# HiSpeedADC.net
KiCad netlist of a schematic drawn in Altium Designer
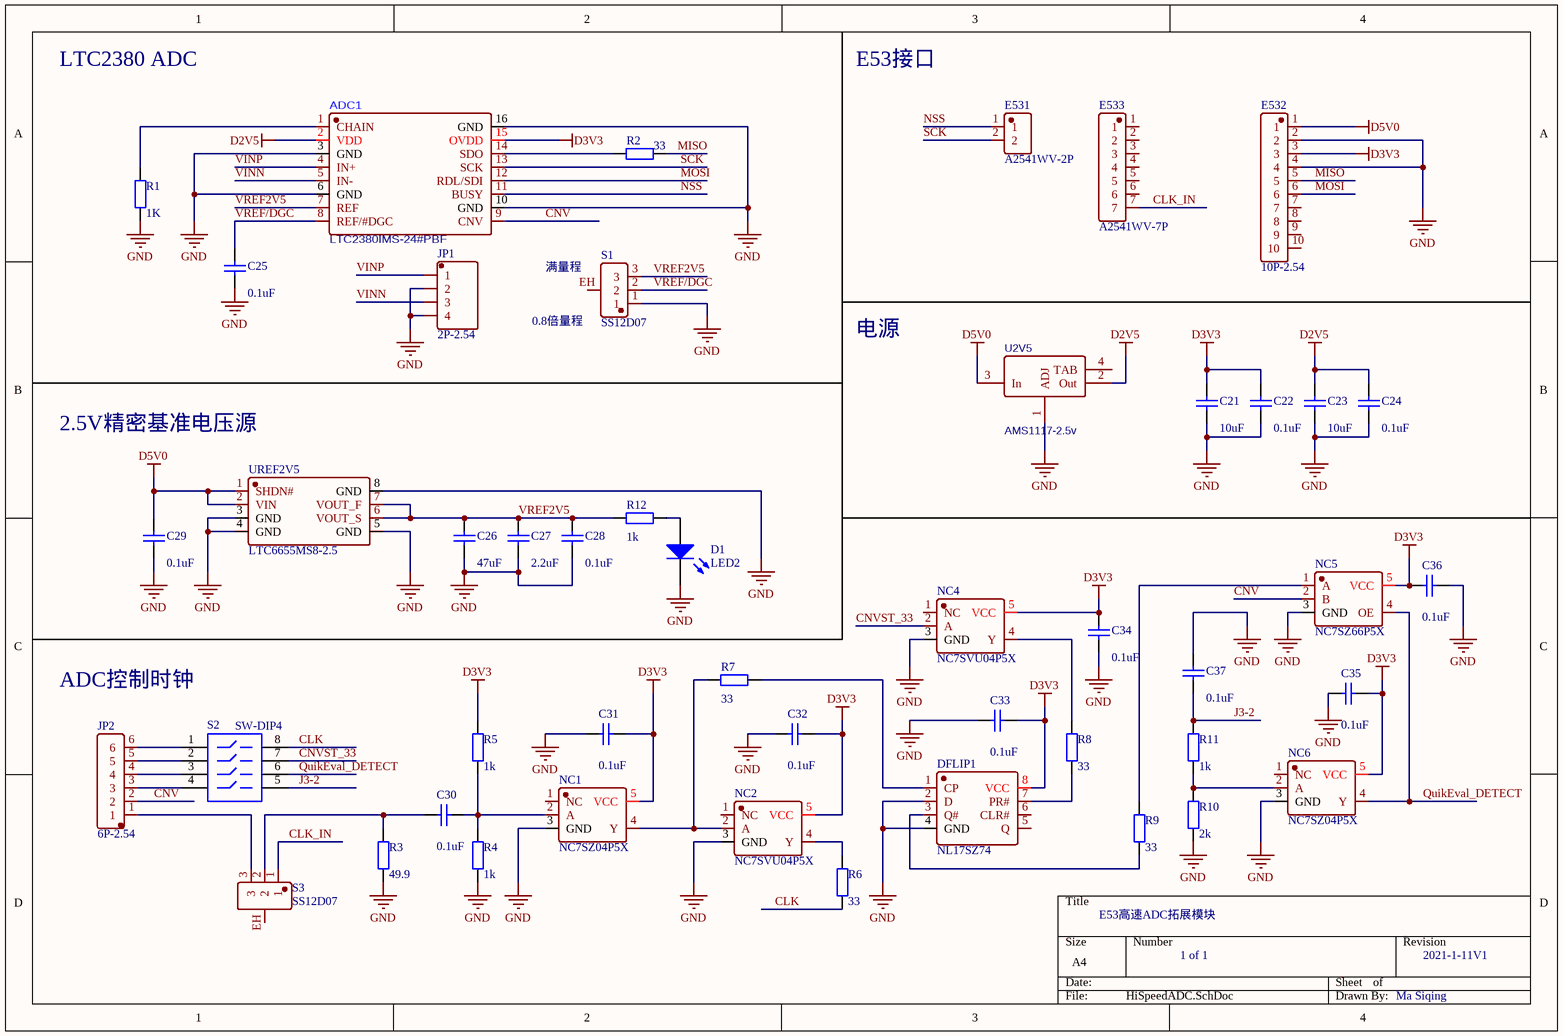
[diagram p0: HiSpeedADC.SchDoc]

(export (version "E")
  (design (tool "Eeschema 10.0.6"))
  (components
    (comp (ref "ADC1")
      (value "LTC2380IMS-24#PBF")
      (footprint "MSOP-16_L4.0-W3.0-P0.50-LS4.9-BL")
      (libsource (lib "NBIoT") (part "LTC2380IMS-24#PBF"))
    )
    (comp (ref "C21")
      (value "10uF")
      (footprint "C1206")
      (description "Capacitor (Semiconductor SIM Model)")
      (fields (field (name "PUBLISHER") "Altium Limited"))
      (libsource (lib "Miscellaneous Devices") (part "Cap Semi"))
    )
    (comp (ref "C22")
      (value "0.1uF")
      (footprint "C1206")
      (description "Capacitor (Semiconductor SIM Model)")
      (fields (field (name "PUBLISHER") "Altium Limited"))
      (libsource (lib "Miscellaneous Devices") (part "Cap Semi"))
    )
    (comp (ref "C23")
      (value "10uF")
      (footprint "C1206")
      (description "Capacitor (Semiconductor SIM Model)")
      (fields (field (name "PUBLISHER") "Altium Limited"))
      (libsource (lib "Miscellaneous Devices") (part "Cap Semi"))
    )
    (comp (ref "C24")
      (value "0.1uF")
      (footprint "C1206")
      (description "Capacitor (Semiconductor SIM Model)")
      (fields (field (name "PUBLISHER") "Altium Limited"))
      (libsource (lib "Miscellaneous Devices") (part "Cap Semi"))
    )
    (comp (ref "C25")
      (value "0.1uF")
      (footprint "C1206")
      (description "Capacitor (Semiconductor SIM Model)")
      (fields (field (name "PUBLISHER") "Altium Limited"))
      (libsource (lib "Miscellaneous Devices") (part "Cap Semi"))
    )
    (comp (ref "C26")
      (value "47uF")
      (footprint "C1206")
      (description "Capacitor (Semiconductor SIM Model)")
      (fields (field (name "PUBLISHER") "Altium Limited"))
      (libsource (lib "Miscellaneous Devices") (part "Cap Semi"))
    )
    (comp (ref "C27")
      (value "2.2uF")
      (footprint "C1206")
      (description "Capacitor (Semiconductor SIM Model)")
      (fields (field (name "PUBLISHER") "Altium Limited"))
      (libsource (lib "Miscellaneous Devices") (part "Cap Semi"))
    )
    (comp (ref "C28")
      (value "0.1uF")
      (footprint "C1206")
      (description "Capacitor (Semiconductor SIM Model)")
      (fields (field (name "PUBLISHER") "Altium Limited"))
      (libsource (lib "Miscellaneous Devices") (part "Cap Semi"))
    )
    (comp (ref "C29")
      (value "0.1uF")
      (footprint "C1206")
      (description "Capacitor (Semiconductor SIM Model)")
      (fields (field (name "PUBLISHER") "Altium Limited"))
      (libsource (lib "Miscellaneous Devices") (part "Cap Semi"))
    )
    (comp (ref "C30")
      (value "0.1uF")
      (footprint "C1206")
      (description "Capacitor (Semiconductor SIM Model)")
      (fields (field (name "PUBLISHER") "Altium Limited"))
      (libsource (lib "Miscellaneous Devices") (part "Cap Semi"))
    )
    (comp (ref "C31")
      (value "0.1uF")
      (footprint "C1206")
      (description "Capacitor (Semiconductor SIM Model)")
      (fields (field (name "PUBLISHER") "Altium Limited"))
      (libsource (lib "Miscellaneous Devices") (part "Cap Semi"))
    )
    (comp (ref "C32")
      (value "0.1uF")
      (footprint "C1206")
      (description "Capacitor (Semiconductor SIM Model)")
      (fields (field (name "PUBLISHER") "Altium Limited"))
      (libsource (lib "Miscellaneous Devices") (part "Cap Semi"))
    )
    (comp (ref "C33")
      (value "0.1uF")
      (footprint "C1206")
      (description "Capacitor (Semiconductor SIM Model)")
      (fields (field (name "PUBLISHER") "Altium Limited"))
      (libsource (lib "Miscellaneous Devices") (part "Cap Semi"))
    )
    (comp (ref "C34")
      (value "0.1uF")
      (footprint "C1206")
      (description "Capacitor (Semiconductor SIM Model)")
      (fields (field (name "PUBLISHER") "Altium Limited"))
      (libsource (lib "Miscellaneous Devices") (part "Cap Semi"))
    )
    (comp (ref "C35")
      (value "0.1uF")
      (footprint "C1206")
      (description "Capacitor (Semiconductor SIM Model)")
      (fields (field (name "PUBLISHER") "Altium Limited"))
      (libsource (lib "Miscellaneous Devices") (part "Cap Semi"))
    )
    (comp (ref "C36")
      (value "0.1uF")
      (footprint "C1206")
      (description "Capacitor (Semiconductor SIM Model)")
      (fields (field (name "PUBLISHER") "Altium Limited"))
      (libsource (lib "Miscellaneous Devices") (part "Cap Semi"))
    )
    (comp (ref "C37")
      (value "0.1uF")
      (footprint "C1206")
      (description "Capacitor (Semiconductor SIM Model)")
      (fields (field (name "PUBLISHER") "Altium Limited"))
      (libsource (lib "Miscellaneous Devices") (part "Cap Semi"))
    )
    (comp (ref "D1")
      (value "LED2")
      (footprint "3.2X1.6X1.1")
      (description "Typical RED, GREEN, YELLOW, AMBER GaAs LED")
      (fields (field (name "PUBLISHER") "Altium Limited"))
      (libsource (lib "Miscellaneous Devices") (part "LED2"))
    )
    (comp (ref "DFLIP1")
      (value "NL17SZ74")
      (footprint "US-8_L2.4-W2.1-P0.50-LS3.2-BR")
      (libsource (lib "NBIoT") (part "NL17SZ74"))
    )
    (comp (ref "E531")
      (value "A2541WV-2P")
      (footprint "HDR-TH_P2.54-H-M_A2541WV-2P")
      (libsource (lib "NBIoT") (part "A2541WV-2P"))
    )
    (comp (ref "E532")
      (value "10P-2.54")
      (footprint "HDR-TH_10P-P2.54-V")
      (libsource (lib "NBIoT") (part "10P-2.54"))
    )
    (comp (ref "E533")
      (value "A2541WV-7P")
      (footprint "HDR-TH_7P-P2.54-V")
      (libsource (lib "NBIoT") (part "A2541WV-7P"))
    )
    (comp (ref "JP1")
      (value "2P-2.54")
      (footprint "HDR-TH_4P-P2.54-V")
      (libsource (lib "NBIoT") (part "2P-2.54"))
    )
    (comp (ref "JP2")
      (value "6P-2.54")
      (footprint "HDR-TH_6P-P2.54-V")
      (libsource (lib "NBIoT") (part "6P-2.54"))
    )
    (comp (ref "NC1")
      (value "NC7SZ04P5X")
      (footprint "SC-70-5_L2.1-W1.3-P0.65-LS2.1-BR")
      (libsource (lib "NBIoT") (part "NC7SZ04P5X"))
    )
    (comp (ref "NC2")
      (value "NC7SVU04P5X")
      (footprint "SC-70-5_L2.1-W1.3-P0.65-LS2.1-BL")
      (libsource (lib "NBIoT") (part "NC7SVU04P5X"))
    )
    (comp (ref "NC4")
      (value "NC7SVU04P5X")
      (footprint "SC-70-5_L2.1-W1.3-P0.65-LS2.1-BL")
      (libsource (lib "NBIoT") (part "NC7SVU04P5X"))
    )
    (comp (ref "NC5")
      (value "NC7SZ66P5X")
      (footprint "SC-70-5_L2.1-W1.3-P0.65-LS2.1-BL")
      (libsource (lib "NBIoT") (part "NC7SZ66P5X"))
    )
    (comp (ref "NC6")
      (value "NC7SZ04P5X")
      (footprint "SC-70-5_L2.1-W1.3-P0.65-LS2.1-BR")
      (libsource (lib "NBIoT") (part "NC7SZ04P5X"))
    )
    (comp (ref "R1")
      (value "1K")
      (footprint "6-0805_N")
      (description "Resistor")
      (fields (field (name "PUBLISHER") "Altium Limited"))
      (libsource (lib "Miscellaneous Devices") (part "Res2"))
    )
    (comp (ref "R2")
      (value "33")
      (footprint "6-0805_N")
      (description "Resistor")
      (fields (field (name "PUBLISHER") "Altium Limited"))
      (libsource (lib "") (part "Res2_1"))
    )
    (comp (ref "R3")
      (value "49.9")
      (footprint "6-0805_N")
      (description "Resistor")
      (fields (field (name "PUBLISHER") "Altium Limited"))
      (libsource (lib "") (part "Res2_2"))
    )
    (comp (ref "R4")
      (value "1k")
      (footprint "6-0805_N")
      (description "Resistor")
      (fields (field (name "PUBLISHER") "Altium Limited"))
      (libsource (lib "") (part "Res2_2"))
    )
    (comp (ref "R5")
      (value "1k")
      (footprint "6-0805_N")
      (description "Resistor")
      (fields (field (name "PUBLISHER") "Altium Limited"))
      (libsource (lib "") (part "Res2_2"))
    )
    (comp (ref "R6")
      (value "33")
      (footprint "6-0805_N")
      (description "Resistor")
      (fields (field (name "PUBLISHER") "Altium Limited"))
      (libsource (lib "Miscellaneous Devices") (part "Res2"))
    )
    (comp (ref "R7")
      (value "33")
      (footprint "6-0805_N")
      (description "Resistor")
      (fields (field (name "PUBLISHER") "Altium Limited"))
      (libsource (lib "") (part "Res2_1"))
    )
    (comp (ref "R8")
      (value "33")
      (footprint "6-0805_N")
      (description "Resistor")
      (fields (field (name "PUBLISHER") "Altium Limited"))
      (libsource (lib "") (part "Res2_2"))
    )
    (comp (ref "R9")
      (value "33")
      (footprint "6-0805_N")
      (description "Resistor")
      (fields (field (name "PUBLISHER") "Altium Limited"))
      (libsource (lib "Miscellaneous Devices") (part "Res2"))
    )
    (comp (ref "R10")
      (value "2k")
      (footprint "6-0805_N")
      (description "Resistor")
      (fields (field (name "PUBLISHER") "Altium Limited"))
      (libsource (lib "Miscellaneous Devices") (part "Res2"))
    )
    (comp (ref "R11")
      (value "1k")
      (footprint "6-0805_N")
      (description "Resistor")
      (fields (field (name "PUBLISHER") "Altium Limited"))
      (libsource (lib "Miscellaneous Devices") (part "Res2"))
    )
    (comp (ref "R12")
      (value "1k")
      (footprint "6-0805_N")
      (description "Resistor")
      (fields (field (name "PUBLISHER") "Altium Limited"))
      (libsource (lib "") (part "Res2_1"))
    )
    (comp (ref "S1")
      (value "SS12D07")
      (footprint "SW-TH_SS-12D07-X-X")
      (libsource (lib "NBIoT") (part "SS12D07"))
    )
    (comp (ref "S2")
      (value "SW-DIP4")
      (footprint "DIP-8")
      (description "DIP Switch")
      (fields (field (name "PUBLISHER") "Altium Limited"))
      (libsource (lib "Miscellaneous Devices") (part "SW-DIP4"))
    )
    (comp (ref "S3")
      (value "SS12D07")
      (footprint "SW-TH_SS-12D07-X-X")
      (libsource (lib "NBIoT") (part "SS12D07"))
    )
    (comp (ref "U2V5")
      (value "AMS1117-2.5v")
      (footprint "SOT-223_L6.7-W3.5-P2.30-BR")
      (fields
        (field (name "BOM_MANUFACTURER PART") "AMS1117-ADJ")
        (field (name "BOM_SUPPLIER PART") "C6188")
        (field (name "CONTRIBUTOR") "GerryChen")
      )
      (libsource (lib "NBIoT") (part "AMS1117-ADJ"))
    )
    (comp (ref "UREF2V5")
      (value "LTC6655MS8-2.5")
      (footprint "US-8_L2.4-W2.1-P0.50-LS3.2-BR")
      (libsource (lib "NBIoT") (part "LTC6655MS8-5"))
    )
  )
  (nets
    (net (code "1") (name "/CLK") (class "Default")
      (node (ref "R6") (pin "1") (pinfunction "1_1") (pintype "passive"))
      (node (ref "S2") (pin "8") (pinfunction "8_8") (pintype "passive"))
    )
    (net (code "2") (name "/CLK_IN") (class "Default")
      (node (ref "E533") (pin "7") (pinfunction "7_7") (pintype "passive"))
      (node (ref "S3") (pin "1") (pinfunction "1_1") (pintype "passive"))
    )
    (net (code "3") (name "/CNV") (class "Default")
      (node (ref "ADC1") (pin "9") (pinfunction "CNV_9") (pintype "passive"))
      (node (ref "JP2") (pin "2") (pinfunction "2_2") (pintype "passive"))
      (node (ref "NC5") (pin "2") (pinfunction "B_2") (pintype "passive"))
    )
    (net (code "4") (name "/CNVST_33") (class "Default")
      (node (ref "NC4") (pin "2") (pinfunction "A_2") (pintype "passive"))
      (node (ref "S2") (pin "7") (pinfunction "7_7") (pintype "passive"))
    )
    (net (code "5") (name "/J3-2") (class "Default")
      (node (ref "C37") (pin "1") (pinfunction "1_1") (pintype "passive"))
      (node (ref "R11") (pin "2") (pinfunction "2_2") (pintype "passive"))
      (node (ref "S2") (pin "5") (pinfunction "5_5") (pintype "passive"))
    )
    (net (code "6") (name "/MISO") (class "Default")
      (node (ref "E532") (pin "5") (pinfunction "5_5") (pintype "passive"))
      (node (ref "R2") (pin "1") (pinfunction "1_1") (pintype "passive"))
    )
    (net (code "7") (name "/MOSI") (class "Default")
      (node (ref "ADC1") (pin "12") (pinfunction "RDL/SDI_12") (pintype "passive"))
      (node (ref "E532") (pin "6") (pinfunction "6_6") (pintype "passive"))
    )
    (net (code "8") (name "/NSS") (class "Default")
      (node (ref "ADC1") (pin "11") (pinfunction "BUSY_11") (pintype "passive"))
      (node (ref "E531") (pin "1") (pinfunction "1_1") (pintype "passive"))
    )
    (net (code "9") (name "/QuikEval_DETECT") (class "Default")
      (node (ref "NC5") (pin "4") (pinfunction "OE_4") (pintype "passive"))
      (node (ref "NC6") (pin "4") (pinfunction "Y_4") (pintype "passive"))
      (node (ref "S2") (pin "6") (pinfunction "6_6") (pintype "passive"))
    )
    (net (code "10") (name "/SCK") (class "Default")
      (node (ref "ADC1") (pin "13") (pinfunction "SCK_13") (pintype "passive"))
      (node (ref "E531") (pin "2") (pinfunction "2_2") (pintype "passive"))
    )
    (net (code "11") (name "/VINN") (class "Default")
      (node (ref "ADC1") (pin "5") (pinfunction "IN-_5") (pintype "passive"))
      (node (ref "JP1") (pin "3") (pinfunction "3_3") (pintype "passive"))
    )
    (net (code "12") (name "/VINP") (class "Default")
      (node (ref "ADC1") (pin "4") (pinfunction "IN+_4") (pintype "passive"))
      (node (ref "JP1") (pin "1") (pinfunction "1_1") (pintype "passive"))
    )
    (net (code "13") (name "/VREF2V5") (class "Default")
      (node (ref "ADC1") (pin "7") (pinfunction "REF_7") (pintype "passive"))
      (node (ref "C26") (pin "1") (pinfunction "1_1") (pintype "passive"))
      (node (ref "C27") (pin "1") (pinfunction "1_1") (pintype "passive"))
      (node (ref "C28") (pin "1") (pinfunction "1_1") (pintype "passive"))
      (node (ref "R12") (pin "2") (pinfunction "2_2") (pintype "passive"))
      (node (ref "S1") (pin "3") (pinfunction "3_3") (pintype "passive"))
      (node (ref "UREF2V5") (pin "6") (pinfunction "VOUT_S_6") (pintype "passive"))
      (node (ref "UREF2V5") (pin "7") (pinfunction "VOUT_F_7") (pintype "passive"))
    )
    (net (code "14") (name "/VREF{slash}DGC") (class "Default")
      (node (ref "ADC1") (pin "8") (pinfunction "REF/#DGC_8") (pintype "passive"))
      (node (ref "C25") (pin "1") (pinfunction "1_1") (pintype "passive"))
      (node (ref "S1") (pin "2") (pinfunction "2_2") (pintype "passive"))
    )
    (net (code "15") (name "D2V5") (class "Default")
      (node (ref "ADC1") (pin "2") (pinfunction "VDD_2") (pintype "passive"))
      (node (ref "C23") (pin "1") (pinfunction "1_1") (pintype "passive"))
      (node (ref "C24") (pin "1") (pinfunction "1_1") (pintype "passive"))
      (node (ref "U2V5") (pin "2") (pinfunction "Out_2") (pintype "passive"))
    )
    (net (code "16") (name "D3V3") (class "Default")
      (node (ref "ADC1") (pin "15") (pinfunction "OVDD_15") (pintype "passive"))
      (node (ref "C21") (pin "1") (pinfunction "1_1") (pintype "passive"))
      (node (ref "C22") (pin "1") (pinfunction "1_1") (pintype "passive"))
      (node (ref "C31") (pin "2") (pinfunction "2_2") (pintype "passive"))
      (node (ref "C32") (pin "2") (pinfunction "2_2") (pintype "passive"))
      (node (ref "C33") (pin "1") (pinfunction "1_1") (pintype "passive"))
      (node (ref "C34") (pin "1") (pinfunction "1_1") (pintype "passive"))
      (node (ref "C35") (pin "2") (pinfunction "2_2") (pintype "passive"))
      (node (ref "C36") (pin "1") (pinfunction "1_1") (pintype "passive"))
      (node (ref "DFLIP1") (pin "8") (pinfunction "VCC_8") (pintype "passive"))
      (node (ref "E532") (pin "3") (pinfunction "3_3") (pintype "passive"))
      (node (ref "NC1") (pin "5") (pinfunction "VCC_5") (pintype "passive"))
      (node (ref "NC2") (pin "5") (pinfunction "VCC_5") (pintype "passive"))
      (node (ref "NC4") (pin "5") (pinfunction "VCC_5") (pintype "passive"))
      (node (ref "NC5") (pin "5") (pinfunction "VCC_5") (pintype "passive"))
      (node (ref "NC6") (pin "5") (pinfunction "VCC_5") (pintype "passive"))
      (node (ref "R5") (pin "1") (pinfunction "1_1") (pintype "passive"))
    )
    (net (code "17") (name "D5V0") (class "Default")
      (node (ref "C29") (pin "1") (pinfunction "1_1") (pintype "passive"))
      (node (ref "E532") (pin "1") (pinfunction "1_1") (pintype "passive"))
      (node (ref "U2V5") (pin "3") (pinfunction "In_3") (pintype "passive"))
      (node (ref "UREF2V5") (pin "1") (pinfunction "SHDN#_1") (pintype "passive"))
      (node (ref "UREF2V5") (pin "2") (pinfunction "VIN_2") (pintype "passive"))
    )
    (net (code "18") (name "GND") (class "Default")
      (node (ref "ADC1") (pin "10") (pinfunction "GND_10") (pintype "passive"))
      (node (ref "ADC1") (pin "16") (pinfunction "GND_16") (pintype "passive"))
      (node (ref "ADC1") (pin "3") (pinfunction "GND_3") (pintype "passive"))
      (node (ref "ADC1") (pin "6") (pinfunction "GND_6") (pintype "passive"))
      (node (ref "C21") (pin "2") (pinfunction "2_2") (pintype "passive"))
      (node (ref "C22") (pin "2") (pinfunction "2_2") (pintype "passive"))
      (node (ref "C23") (pin "2") (pinfunction "2_2") (pintype "passive"))
      (node (ref "C24") (pin "2") (pinfunction "2_2") (pintype "passive"))
      (node (ref "C25") (pin "2") (pinfunction "2_2") (pintype "passive"))
      (node (ref "C26") (pin "2") (pinfunction "2_2") (pintype "passive"))
      (node (ref "C27") (pin "2") (pinfunction "2_2") (pintype "passive"))
      (node (ref "C28") (pin "2") (pinfunction "2_2") (pintype "passive"))
      (node (ref "C29") (pin "2") (pinfunction "2_2") (pintype "passive"))
      (node (ref "C31") (pin "1") (pinfunction "1_1") (pintype "passive"))
      (node (ref "C32") (pin "1") (pinfunction "1_1") (pintype "passive"))
      (node (ref "C33") (pin "2") (pinfunction "2_2") (pintype "passive"))
      (node (ref "C34") (pin "2") (pinfunction "2_2") (pintype "passive"))
      (node (ref "C35") (pin "1") (pinfunction "1_1") (pintype "passive"))
      (node (ref "C36") (pin "2") (pinfunction "2_2") (pintype "passive"))
      (node (ref "C37") (pin "2") (pinfunction "2_2") (pintype "passive"))
      (node (ref "D1") (pin "2") (pinfunction "K_2") (pintype "passive"))
      (node (ref "DFLIP1") (pin "2") (pinfunction "D_2") (pintype "passive"))
      (node (ref "DFLIP1") (pin "4") (pinfunction "GND_4") (pintype "passive"))
      (node (ref "E532") (pin "2") (pinfunction "2_2") (pintype "passive"))
      (node (ref "E532") (pin "4") (pinfunction "4_4") (pintype "passive"))
      (node (ref "JP1") (pin "2") (pinfunction "2_2") (pintype "passive"))
      (node (ref "JP1") (pin "4") (pinfunction "4_4") (pintype "passive"))
      (node (ref "NC1") (pin "3") (pinfunction "GND_3") (pintype "passive"))
      (node (ref "NC2") (pin "3") (pinfunction "GND_3") (pintype "passive"))
      (node (ref "NC4") (pin "3") (pinfunction "GND_3") (pintype "passive"))
      (node (ref "NC5") (pin "3") (pinfunction "GND_3") (pintype "passive"))
      (node (ref "NC6") (pin "3") (pinfunction "GND_3") (pintype "passive"))
      (node (ref "R1") (pin "1") (pinfunction "1_1") (pintype "passive"))
      (node (ref "R10") (pin "1") (pinfunction "1_1") (pintype "passive"))
      (node (ref "R3") (pin "2") (pinfunction "2_2") (pintype "passive"))
      (node (ref "R4") (pin "2") (pinfunction "2_2") (pintype "passive"))
      (node (ref "S1") (pin "1") (pinfunction "1_1") (pintype "passive"))
      (node (ref "U2V5") (pin "1") (pinfunction "ADJ_1") (pintype "passive"))
      (node (ref "UREF2V5") (pin "3") (pinfunction "GND_3") (pintype "passive"))
      (node (ref "UREF2V5") (pin "4") (pinfunction "GND_4") (pintype "passive"))
      (node (ref "UREF2V5") (pin "5") (pinfunction "GND_5") (pintype "passive"))
      (node (ref "UREF2V5") (pin "8") (pinfunction "GND_8") (pintype "passive"))
    )
    (net (code "19") (name "Net-(ADC1-CHAIN)") (class "Default")
      (node (ref "ADC1") (pin "1") (pinfunction "CHAIN_1") (pintype "passive"))
      (node (ref "R1") (pin "2") (pinfunction "2_2") (pintype "passive"))
    )
    (net (code "20") (name "Net-(ADC1-SDO)") (class "Default")
      (node (ref "ADC1") (pin "14") (pinfunction "SDO_14") (pintype "passive"))
      (node (ref "R2") (pin "2") (pinfunction "2_2") (pintype "passive"))
    )
    (net (code "21") (name "Net-(C30-Pad1)") (class "Default")
      (node (ref "C30") (pin "1") (pinfunction "1_1") (pintype "passive"))
      (node (ref "R3") (pin "1") (pinfunction "1_1") (pintype "passive"))
      (node (ref "S3") (pin "2") (pinfunction "2_2") (pintype "passive"))
    )
    (net (code "22") (name "Net-(D1-A)") (class "Default")
      (node (ref "D1") (pin "1") (pinfunction "A_1") (pintype "passive"))
      (node (ref "R12") (pin "1") (pinfunction "1_1") (pintype "passive"))
    )
    (net (code "23") (name "Net-(DFLIP1-CP)") (class "Default")
      (node (ref "DFLIP1") (pin "1") (pinfunction "CP_1") (pintype "passive"))
      (node (ref "R7") (pin "1") (pinfunction "1_1") (pintype "passive"))
    )
    (net (code "24") (name "Net-(DFLIP1-PR#)") (class "Default")
      (node (ref "DFLIP1") (pin "7") (pinfunction "PR#_7") (pintype "passive"))
      (node (ref "R8") (pin "2") (pinfunction "2_2") (pintype "passive"))
    )
    (net (code "25") (name "Net-(DFLIP1-Q#)") (class "Default")
      (node (ref "DFLIP1") (pin "3") (pinfunction "Q#_3") (pintype "passive"))
      (node (ref "R9") (pin "1") (pinfunction "1_1") (pintype "passive"))
    )
    (net (code "26") (name "Net-(JP2-Pad1)") (class "Default")
      (node (ref "JP2") (pin "1") (pinfunction "1_1") (pintype "passive"))
      (node (ref "S3") (pin "3") (pinfunction "3_3") (pintype "passive"))
    )
    (net (code "27") (name "Net-(JP2-Pad3)") (class "Default")
      (node (ref "JP2") (pin "3") (pinfunction "3_3") (pintype "passive"))
      (node (ref "S2") (pin "4") (pinfunction "4_4") (pintype "passive"))
    )
    (net (code "28") (name "Net-(JP2-Pad4)") (class "Default")
      (node (ref "JP2") (pin "4") (pinfunction "4_4") (pintype "passive"))
      (node (ref "S2") (pin "3") (pinfunction "3_3") (pintype "passive"))
    )
    (net (code "29") (name "Net-(JP2-Pad5)") (class "Default")
      (node (ref "JP2") (pin "5") (pinfunction "5_5") (pintype "passive"))
      (node (ref "S2") (pin "2") (pinfunction "2_2") (pintype "passive"))
    )
    (net (code "30") (name "Net-(JP2-Pad6)") (class "Default")
      (node (ref "JP2") (pin "6") (pinfunction "6_6") (pintype "passive"))
      (node (ref "S2") (pin "1") (pinfunction "1_1") (pintype "passive"))
    )
    (net (code "31") (name "Net-(NC1-A)") (class "Default")
      (node (ref "C30") (pin "2") (pinfunction "2_2") (pintype "passive"))
      (node (ref "NC1") (pin "2") (pinfunction "A_2") (pintype "passive"))
      (node (ref "R4") (pin "1") (pinfunction "1_1") (pintype "passive"))
      (node (ref "R5") (pin "2") (pinfunction "2_2") (pintype "passive"))
    )
    (net (code "32") (name "Net-(NC1-Y)") (class "Default")
      (node (ref "NC1") (pin "4") (pinfunction "Y_4") (pintype "passive"))
      (node (ref "NC2") (pin "2") (pinfunction "A_2") (pintype "passive"))
      (node (ref "R7") (pin "2") (pinfunction "2_2") (pintype "passive"))
    )
    (net (code "33") (name "Net-(NC2-Y)") (class "Default")
      (node (ref "NC2") (pin "4") (pinfunction "Y_4") (pintype "passive"))
      (node (ref "R6") (pin "2") (pinfunction "2_2") (pintype "passive"))
    )
    (net (code "34") (name "Net-(NC4-Y)") (class "Default")
      (node (ref "NC4") (pin "4") (pinfunction "Y_4") (pintype "passive"))
      (node (ref "R8") (pin "1") (pinfunction "1_1") (pintype "passive"))
    )
    (net (code "35") (name "Net-(NC5-A)") (class "Default")
      (node (ref "NC5") (pin "1") (pinfunction "A_1") (pintype "passive"))
      (node (ref "R9") (pin "2") (pinfunction "2_2") (pintype "passive"))
    )
    (net (code "36") (name "Net-(NC6-A)") (class "Default")
      (node (ref "NC6") (pin "2") (pinfunction "A_2") (pintype "passive"))
      (node (ref "R10") (pin "2") (pinfunction "2_2") (pintype "passive"))
      (node (ref "R11") (pin "1") (pinfunction "1_1") (pintype "passive"))
    )
    (net (code "37") (name "unconnected-(DFLIP1-CLR#-Pad6)") (class "Default")
      (node (ref "DFLIP1") (pin "6") (pinfunction "CLR#_6") (pintype "passive"))
    )
    (net (code "38") (name "unconnected-(DFLIP1-Q-Pad5)") (class "Default")
      (node (ref "DFLIP1") (pin "5") (pinfunction "Q_5") (pintype "passive"))
    )
    (net (code "39") (name "unconnected-(E532-Pad7)") (class "Default")
      (node (ref "E532") (pin "7") (pinfunction "7_7") (pintype "passive"))
    )
    (net (code "40") (name "unconnected-(E532-Pad8)") (class "Default")
      (node (ref "E532") (pin "8") (pinfunction "8_8") (pintype "passive"))
    )
    (net (code "41") (name "unconnected-(E532-Pad9)") (class "Default")
      (node (ref "E532") (pin "9") (pinfunction "9_9") (pintype "passive"))
    )
    (net (code "42") (name "unconnected-(E532-Pad10)") (class "Default")
      (node (ref "E532") (pin "10") (pinfunction "10_10") (pintype "passive"))
    )
    (net (code "43") (name "unconnected-(E533-Pad1)") (class "Default")
      (node (ref "E533") (pin "1") (pinfunction "1_1") (pintype "passive"))
    )
    (net (code "44") (name "unconnected-(E533-Pad2)") (class "Default")
      (node (ref "E533") (pin "2") (pinfunction "2_2") (pintype "passive"))
    )
    (net (code "45") (name "unconnected-(E533-Pad3)") (class "Default")
      (node (ref "E533") (pin "3") (pinfunction "3_3") (pintype "passive"))
    )
    (net (code "46") (name "unconnected-(E533-Pad4)") (class "Default")
      (node (ref "E533") (pin "4") (pinfunction "4_4") (pintype "passive"))
    )
    (net (code "47") (name "unconnected-(E533-Pad5)") (class "Default")
      (node (ref "E533") (pin "5") (pinfunction "5_5") (pintype "passive"))
    )
    (net (code "48") (name "unconnected-(E533-Pad6)") (class "Default")
      (node (ref "E533") (pin "6") (pinfunction "6_6") (pintype "passive"))
    )
    (net (code "49") (name "unconnected-(NC1-NC-Pad1)") (class "Default")
      (node (ref "NC1") (pin "1") (pinfunction "NC_1") (pintype "passive"))
    )
    (net (code "50") (name "unconnected-(NC2-NC-Pad1)") (class "Default")
      (node (ref "NC2") (pin "1") (pinfunction "NC_1") (pintype "passive"))
    )
    (net (code "51") (name "unconnected-(NC4-NC-Pad1)") (class "Default")
      (node (ref "NC4") (pin "1") (pinfunction "NC_1") (pintype "passive"))
    )
    (net (code "52") (name "unconnected-(NC6-NC-Pad1)") (class "Default")
      (node (ref "NC6") (pin "1") (pinfunction "NC_1") (pintype "passive"))
    )
    (net (code "53") (name "unconnected-(S1-PadEH)") (class "Default")
      (node (ref "S1") (pin "EH") (pinfunction "EH_EH") (pintype "passive"))
    )
    (net (code "54") (name "unconnected-(S3-PadEH)") (class "Default")
      (node (ref "S3") (pin "EH") (pinfunction "EH_EH") (pintype "passive"))
    )
    (net (code "55") (name "unconnected-(U2V5-TAB-Pad4)") (class "Default")
      (node (ref "U2V5") (pin "4") (pinfunction "TAB_4") (pintype "passive"))
    )
  )
)
